# ardBeeQueen.net
KiCad netlist of a schematic drawn in EAGLE
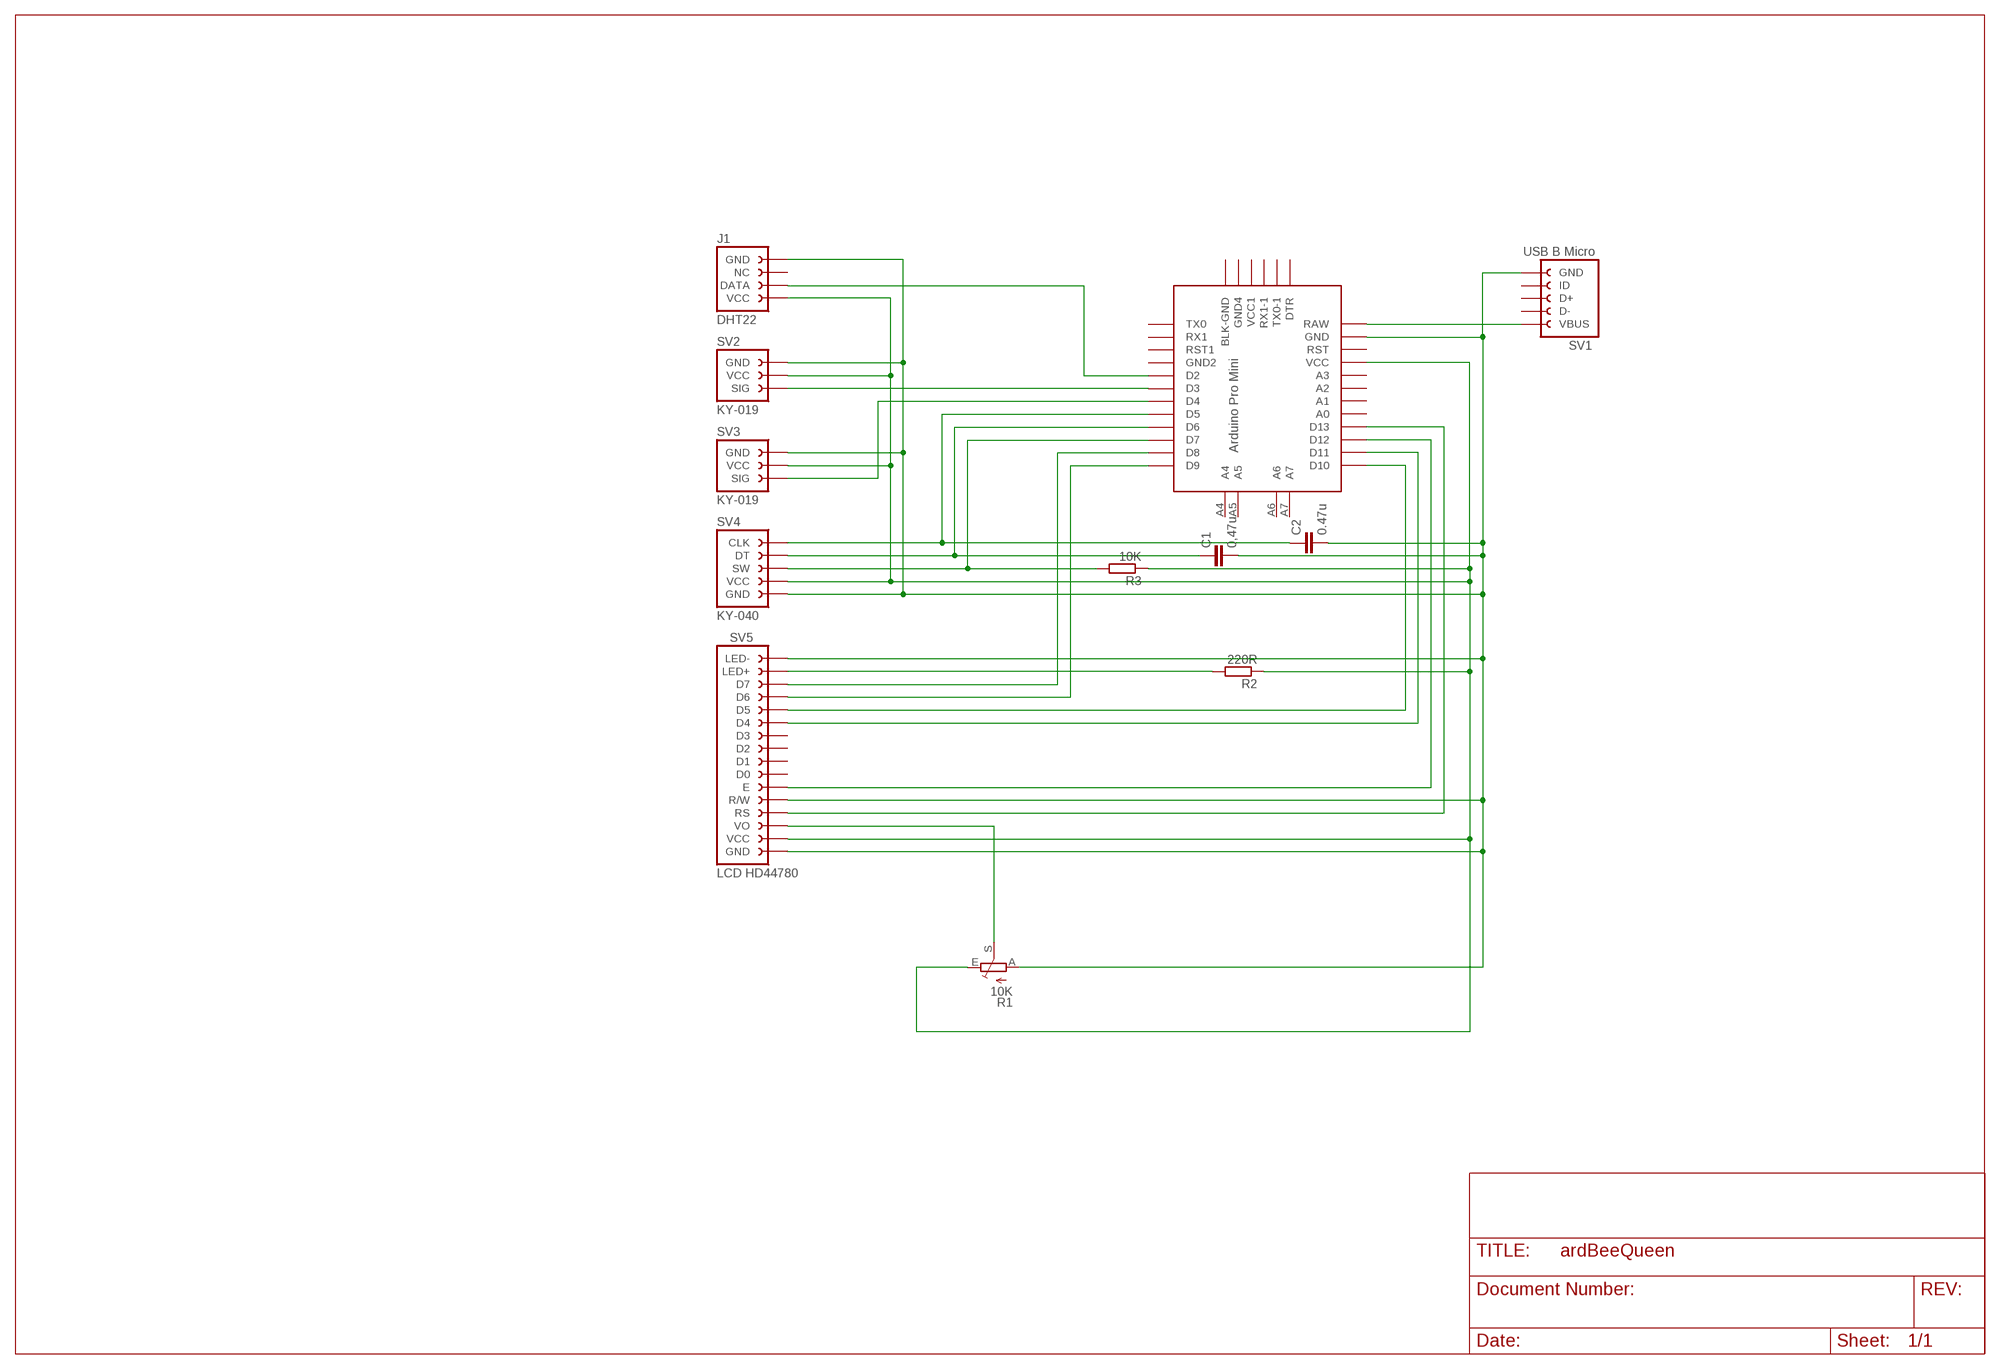
[diagram p0: schematic, sheet 1]

(export (version "E")
  (design (tool "Eeschema 10.0.6"))
  (components
    (comp (ref "C1")
      (value "0,47u")
      (footprint "eagle-import:C050-024X044")
      (libsource (lib "eagle-import") (part "C-EU050-024X044"))
    )
    (comp (ref "C2")
      (value "0.47u")
      (footprint "eagle-import:C050-024X044")
      (libsource (lib "eagle-import") (part "C-EU050-024X044"))
    )
    (comp (ref "J1")
      (value "DHT22_4-PIN_FEMALE_HEADERPTH")
      (footprint "eagle-import:DHT22_4-PIN_FEMALE_HEADER")
      (libsource (lib "eagle-import") (part "DHT22_4-PIN_FEMALE_HEADERPTH"))
    )
    (comp (ref "R1")
      (value "10K")
      (footprint "eagle-import:B25P")
      (libsource (lib "eagle-import") (part "TRIM_EU-B25P"))
    )
    (comp (ref "R2")
      (value "220R")
      (footprint "eagle-import:0207_10")
      (libsource (lib "eagle-import") (part "R-EU_0207/10"))
    )
    (comp (ref "R3")
      (value "10K")
      (footprint "eagle-import:0207_10")
      (libsource (lib "eagle-import") (part "R-EU_0207/10"))
    )
    (comp (ref "SV1")
      (value "MICROUSB_B_BREAKOUT_5-PIN_FEMALE_HEADERWITH_MOUNT_HOLES")
      (footprint "eagle-import:MICROUSB_B_BREAKOUT_5-PIN_FEMALE_HEADER_W_MOUNT_HOLES")
      (libsource (lib "eagle-import") (part "MICROUSB_B_BREAKOUT_5-PIN_FEMALE_HEADERWITH_MOUNT_HOLES"))
    )
    (comp (ref "SV2")
      (value "KY-019_3-PIN_FEMALE_HEADER")
      (footprint "eagle-import:KY-019_3-PIN_FEMALE_HEADER")
      (libsource (lib "eagle-import") (part "KY-019_3-PIN_FEMALE_HEADER"))
    )
    (comp (ref "SV3")
      (value "KY-019_3-PIN_FEMALE_HEADER")
      (footprint "eagle-import:KY-019_3-PIN_FEMALE_HEADER")
      (libsource (lib "eagle-import") (part "KY-019_3-PIN_FEMALE_HEADER"))
    )
    (comp (ref "SV4")
      (value "KY-040_5-PIN_FEMALE_HEADER")
      (footprint "eagle-import:KY-040_5-PIN_FEMALE_HEADER")
      (libsource (lib "eagle-import") (part "KY-040_5-PIN_FEMALE_HEADER"))
    )
    (comp (ref "SV5")
      (value "LCD-HD44780-16-PIN_FEMALE_HEADER")
      (footprint "eagle-import:LCD-HD44780-16-PIN_FEMALE_HEADER")
      (libsource (lib "eagle-import") (part "LCD-HD44780-16-PIN_FEMALE_HEADER"))
    )
    (comp (ref "U$1")
      (value "ARDUINO_PRO_MINI-2")
      (footprint "eagle-import:ARDUINO_PRO_MINI-2")
      (libsource (lib "eagle-import") (part "ARDUINO_PRO_MINI-2"))
    )
  )
  (nets
    (net (code "1") (name "Net-(C1-Pad1)") (class "Default")
      (node (ref "C1") (pin "1") (pinfunction "1_1") (pintype "passive"))
      (node (ref "SV4") (pin "DT") (pinfunction "DT_DT") (pintype "passive"))
      (node (ref "U$1") (pin "D6") (pinfunction "D6_D6") (pintype "bidirectional"))
    )
    (net (code "2") (name "Net-(C1-Pad2)") (class "Default")
      (node (ref "C1") (pin "2") (pinfunction "2_2") (pintype "passive"))
      (node (ref "C2") (pin "2") (pinfunction "2_2") (pintype "passive"))
      (node (ref "J1") (pin "GND") (pinfunction "GND_GND") (pintype "passive"))
      (node (ref "R1") (pin "A") (pinfunction "A_A") (pintype "passive"))
      (node (ref "SV1") (pin "GND") (pinfunction "GND_GND") (pintype "passive"))
      (node (ref "SV2") (pin "GND") (pinfunction "GND_GND") (pintype "passive"))
      (node (ref "SV3") (pin "GND") (pinfunction "GND_GND") (pintype "passive"))
      (node (ref "SV4") (pin "GND") (pinfunction "GND_GND") (pintype "passive"))
      (node (ref "SV5") (pin "GND") (pinfunction "GND_GND") (pintype "passive"))
      (node (ref "SV5") (pin "LED-") (pinfunction "LED-_LED-") (pintype "passive"))
      (node (ref "SV5") (pin "R/W") (pinfunction "R/W_R/W") (pintype "passive"))
      (node (ref "U$1") (pin "GND") (pinfunction "GND_GND") (pintype "bidirectional"))
    )
    (net (code "3") (name "Net-(C2-Pad1)") (class "Default")
      (node (ref "C2") (pin "1") (pinfunction "1_1") (pintype "passive"))
      (node (ref "SV4") (pin "CLK") (pinfunction "CLK_CLK") (pintype "passive"))
      (node (ref "U$1") (pin "D5") (pinfunction "D5_D5") (pintype "bidirectional"))
    )
    (net (code "4") (name "Net-(J1-PadDATA)") (class "Default")
      (node (ref "J1") (pin "DATA") (pinfunction "DATA_DATA") (pintype "passive"))
      (node (ref "U$1") (pin "D2") (pinfunction "D2_D2") (pintype "bidirectional"))
    )
    (net (code "5") (name "Net-(J1-PadVCC)") (class "Default")
      (node (ref "J1") (pin "VCC") (pinfunction "VCC_VCC") (pintype "passive"))
      (node (ref "R1") (pin "E") (pinfunction "E_E") (pintype "passive"))
      (node (ref "R2") (pin "1") (pinfunction "1_1") (pintype "passive"))
      (node (ref "R3") (pin "1") (pinfunction "1_1") (pintype "passive"))
      (node (ref "SV2") (pin "VCC") (pinfunction "VCC_VCC") (pintype "passive"))
      (node (ref "SV3") (pin "VCC") (pinfunction "VCC_VCC") (pintype "passive"))
      (node (ref "SV4") (pin "VCC") (pinfunction "VCC_VCC") (pintype "passive"))
      (node (ref "SV5") (pin "VCC") (pinfunction "VCC_VCC") (pintype "passive"))
      (node (ref "U$1") (pin "VCC") (pinfunction "VCC_VCC") (pintype "bidirectional"))
    )
    (net (code "6") (name "Net-(R1-PadS)") (class "Default")
      (node (ref "R1") (pin "S") (pinfunction "S_S") (pintype "passive"))
      (node (ref "SV5") (pin "VO") (pinfunction "VO_VO") (pintype "passive"))
    )
    (net (code "7") (name "Net-(R2-Pad2)") (class "Default")
      (node (ref "R2") (pin "2") (pinfunction "2_2") (pintype "passive"))
      (node (ref "SV5") (pin "LED+") (pinfunction "LED+_LED+") (pintype "passive"))
    )
    (net (code "8") (name "Net-(R3-Pad2)") (class "Default")
      (node (ref "R3") (pin "2") (pinfunction "2_2") (pintype "passive"))
      (node (ref "SV4") (pin "SW") (pinfunction "SW_SW") (pintype "passive"))
      (node (ref "U$1") (pin "D7") (pinfunction "D7_D7") (pintype "bidirectional"))
    )
    (net (code "9") (name "Net-(SV1-PadVBUS)") (class "Default")
      (node (ref "SV1") (pin "VBUS") (pinfunction "VBUS_VBUS") (pintype "passive"))
      (node (ref "U$1") (pin "RAW") (pinfunction "RAW_RAW") (pintype "bidirectional"))
    )
    (net (code "10") (name "Net-(SV2-PadSIG)") (class "Default")
      (node (ref "SV2") (pin "SIG") (pinfunction "SIG_SIG") (pintype "passive"))
      (node (ref "U$1") (pin "D3") (pinfunction "D3_D3") (pintype "bidirectional"))
    )
    (net (code "11") (name "Net-(SV3-PadSIG)") (class "Default")
      (node (ref "SV3") (pin "SIG") (pinfunction "SIG_SIG") (pintype "passive"))
      (node (ref "U$1") (pin "D4") (pinfunction "D4_D4") (pintype "bidirectional"))
    )
    (net (code "12") (name "Net-(SV5-PadD4)") (class "Default")
      (node (ref "SV5") (pin "D4") (pinfunction "D4_D4") (pintype "passive"))
      (node (ref "U$1") (pin "D11") (pinfunction "D11_D11") (pintype "bidirectional"))
    )
    (net (code "13") (name "Net-(SV5-PadD5)") (class "Default")
      (node (ref "SV5") (pin "D5") (pinfunction "D5_D5") (pintype "passive"))
      (node (ref "U$1") (pin "D10") (pinfunction "D10_D10") (pintype "bidirectional"))
    )
    (net (code "14") (name "Net-(SV5-PadD6)") (class "Default")
      (node (ref "SV5") (pin "D6") (pinfunction "D6_D6") (pintype "passive"))
      (node (ref "U$1") (pin "D9") (pinfunction "D9_D9") (pintype "bidirectional"))
    )
    (net (code "15") (name "Net-(SV5-PadD7)") (class "Default")
      (node (ref "SV5") (pin "D7") (pinfunction "D7_D7") (pintype "passive"))
      (node (ref "U$1") (pin "D8") (pinfunction "D8_D8") (pintype "bidirectional"))
    )
    (net (code "16") (name "Net-(SV5-PadE)") (class "Default")
      (node (ref "SV5") (pin "E") (pinfunction "E_E") (pintype "passive"))
      (node (ref "U$1") (pin "D12") (pinfunction "D12_D12") (pintype "bidirectional"))
    )
    (net (code "17") (name "Net-(SV5-PadRS)") (class "Default")
      (node (ref "SV5") (pin "RS") (pinfunction "RS_RS") (pintype "passive"))
      (node (ref "U$1") (pin "D13") (pinfunction "D13_D13") (pintype "bidirectional"))
    )
    (net (code "18") (name "unconnected-(J1-PadNC)") (class "Default")
      (node (ref "J1") (pin "NC") (pinfunction "NC_NC") (pintype "passive"))
    )
    (net (code "19") (name "unconnected-(SV1-PadD+)") (class "Default")
      (node (ref "SV1") (pin "D+") (pinfunction "D+_D+") (pintype "passive"))
    )
    (net (code "20") (name "unconnected-(SV1-PadD-)") (class "Default")
      (node (ref "SV1") (pin "D-") (pinfunction "D-_D-") (pintype "passive"))
    )
    (net (code "21") (name "unconnected-(SV1-PadID)") (class "Default")
      (node (ref "SV1") (pin "ID") (pinfunction "ID_ID") (pintype "passive"))
    )
    (net (code "22") (name "unconnected-(SV5-PadD0)") (class "Default")
      (node (ref "SV5") (pin "D0") (pinfunction "D0_D0") (pintype "passive"))
    )
    (net (code "23") (name "unconnected-(SV5-PadD1)") (class "Default")
      (node (ref "SV5") (pin "D1") (pinfunction "D1_D1") (pintype "passive"))
    )
    (net (code "24") (name "unconnected-(SV5-PadD2)") (class "Default")
      (node (ref "SV5") (pin "D2") (pinfunction "D2_D2") (pintype "passive"))
    )
    (net (code "25") (name "unconnected-(SV5-PadD3)") (class "Default")
      (node (ref "SV5") (pin "D3") (pinfunction "D3_D3") (pintype "passive"))
    )
    (net (code "26") (name "unconnected-(U$1-GND2-PadGND1)") (class "Default")
      (node (ref "U$1") (pin "GND1") (pinfunction "GND2_GND1") (pintype "bidirectional"))
    )
    (net (code "27") (name "unconnected-(U$1-GND4-PadGND3)") (class "Default")
      (node (ref "U$1") (pin "GND3") (pinfunction "GND4_GND3") (pintype "bidirectional"))
    )
    (net (code "28") (name "unconnected-(U$1-PadA0)") (class "Default")
      (node (ref "U$1") (pin "A0") (pinfunction "A0_A0") (pintype "bidirectional"))
    )
    (net (code "29") (name "unconnected-(U$1-PadA1)") (class "Default")
      (node (ref "U$1") (pin "A1") (pinfunction "A1_A1") (pintype "bidirectional"))
    )
    (net (code "30") (name "unconnected-(U$1-PadA2)") (class "Default")
      (node (ref "U$1") (pin "A2") (pinfunction "A2_A2") (pintype "bidirectional"))
    )
    (net (code "31") (name "unconnected-(U$1-PadA3)") (class "Default")
      (node (ref "U$1") (pin "A3") (pinfunction "A3_A3") (pintype "bidirectional"))
    )
    (net (code "32") (name "unconnected-(U$1-PadA4)") (class "Default")
      (node (ref "U$1") (pin "A4") (pinfunction "A4_A4") (pintype "bidirectional"))
    )
    (net (code "33") (name "unconnected-(U$1-PadA5)") (class "Default")
      (node (ref "U$1") (pin "A5") (pinfunction "A5_A5") (pintype "bidirectional"))
    )
    (net (code "34") (name "unconnected-(U$1-PadA6)") (class "Default")
      (node (ref "U$1") (pin "A6") (pinfunction "A6_A6") (pintype "bidirectional"))
    )
    (net (code "35") (name "unconnected-(U$1-PadA7)") (class "Default")
      (node (ref "U$1") (pin "A7") (pinfunction "A7_A7") (pintype "bidirectional"))
    )
    (net (code "36") (name "unconnected-(U$1-PadBLK-GND)") (class "Default")
      (node (ref "U$1") (pin "BLK-GND") (pinfunction "BLK-GND_BLK-GND") (pintype "bidirectional"))
    )
    (net (code "37") (name "unconnected-(U$1-PadDTR)") (class "Default")
      (node (ref "U$1") (pin "DTR") (pinfunction "DTR_DTR") (pintype "bidirectional"))
    )
    (net (code "38") (name "unconnected-(U$1-PadRST)") (class "Default")
      (node (ref "U$1") (pin "RST") (pinfunction "RST_RST") (pintype "bidirectional"))
    )
    (net (code "39") (name "unconnected-(U$1-PadRST1)") (class "Default")
      (node (ref "U$1") (pin "RST1") (pinfunction "RST1_RST1") (pintype "bidirectional"))
    )
    (net (code "40") (name "unconnected-(U$1-PadRX1)") (class "Default")
      (node (ref "U$1") (pin "RX1") (pinfunction "RX1_RX1") (pintype "bidirectional"))
    )
    (net (code "41") (name "unconnected-(U$1-PadRX1-1)") (class "Default")
      (node (ref "U$1") (pin "RX1-1") (pinfunction "RX1-1_RX1-1") (pintype "bidirectional"))
    )
    (net (code "42") (name "unconnected-(U$1-PadTX0)") (class "Default")
      (node (ref "U$1") (pin "TX0") (pinfunction "TX0_TX0") (pintype "bidirectional"))
    )
    (net (code "43") (name "unconnected-(U$1-PadTX0-1)") (class "Default")
      (node (ref "U$1") (pin "TX0-1") (pinfunction "TX0-1_TX0-1") (pintype "bidirectional"))
    )
    (net (code "44") (name "unconnected-(U$1-PadVCC1)") (class "Default")
      (node (ref "U$1") (pin "VCC1") (pinfunction "VCC1_VCC1") (pintype "bidirectional"))
    )
  )
)
